# MCU.net
KiCad netlist of a schematic drawn in Altium Designer
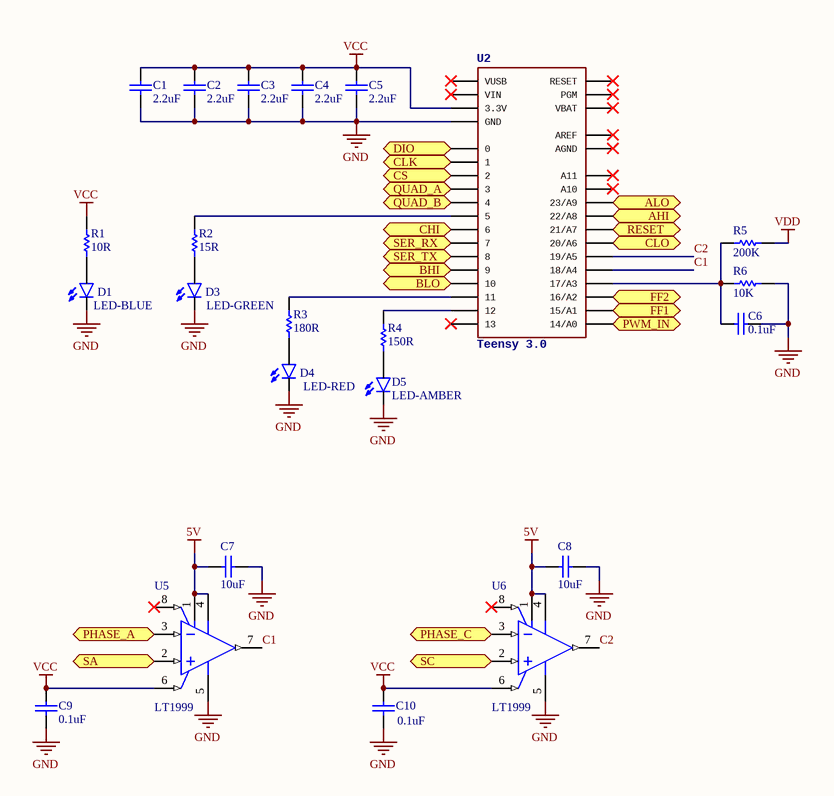
[diagram p0: MCU.SchDoc]

(export (version "E")
  (design (tool "Eeschema 10.0.6"))
  (components
    (comp (ref "C1")
      (value "2.2uF")
      (footprint "CAPC0603(1608)55_N")
      (description "CAP 2.2uF 16V Â±10% 0603 (1608 Metric) Thickness 0.55mm SMD")
      (fields (field (name "TOLERANCE") "Â±10%"))
      (libsource (lib "Altium Content Vault") (part "CMP-1035-02762-1"))
    )
    (comp (ref "C2")
      (value "2.2uF")
      (footprint "CAPC0603(1608)55_N")
      (description "CAP 2.2uF 16V Â±10% 0603 (1608 Metric) Thickness 0.55mm SMD")
      (fields (field (name "TOLERANCE") "Â±10%"))
      (libsource (lib "Altium Content Vault") (part "CMP-1035-02762-1"))
    )
    (comp (ref "C3")
      (value "2.2uF")
      (footprint "CAPC0603(1608)55_N")
      (description "CAP 2.2uF 16V Â±10% 0603 (1608 Metric) Thickness 0.55mm SMD")
      (fields (field (name "TOLERANCE") "Â±10%"))
      (libsource (lib "Altium Content Vault") (part "CMP-1035-02762-1"))
    )
    (comp (ref "C4")
      (value "2.2uF")
      (footprint "CAPC0603(1608)55_N")
      (description "CAP 2.2uF 16V Â±10% 0603 (1608 Metric) Thickness 0.55mm SMD")
      (fields (field (name "TOLERANCE") "Â±10%"))
      (libsource (lib "Altium Content Vault") (part "CMP-1035-02762-1"))
    )
    (comp (ref "C5")
      (value "2.2uF")
      (footprint "CAPC0603(1608)55_N")
      (description "CAP 2.2uF 16V Â±10% 0603 (1608 Metric) Thickness 0.55mm SMD")
      (fields (field (name "TOLERANCE") "Â±10%"))
      (libsource (lib "Altium Content Vault") (part "CMP-1035-02762-1"))
    )
    (comp (ref "C6")
      (value "0.1uF")
      (footprint "CAPC0603(1608)100_L")
      (description "CAP 100nF 50V Â±5% 0603 (1608 Metric) Thickness 1mm SMD")
      (fields (field (name "TOLERANCE") "Â±5%"))
      (libsource (lib "Altium Content Vault") (part "CMP-1035-02591-1"))
    )
    (comp (ref "C7")
      (value "10uF")
      (footprint "CAPC0603(1608)100_L")
      (description "CAP 10uF 6.3V Â±10% 0603 (1608 Metric) Thickness 1mm SMD")
      (fields (field (name "TOLERANCE") "Â±10%"))
      (libsource (lib "Altium Content Vault") (part "CMP-1035-02796-1"))
    )
    (comp (ref "C8")
      (value "10uF")
      (footprint "CAPC0603(1608)100_M")
      (description "CAP 10uF 6.3V Â±20% 0603 (1608 Metric) Thickness 1mm SMD")
      (fields (field (name "TOLERANCE") "Â±20%"))
      (libsource (lib "Altium Content Vault") (part "CMP-1035-02797-1"))
    )
    (comp (ref "C9")
      (value "0.1uF")
      (footprint "CAPC0603(1608)100_L")
      (description "CAP 100nF 6.3V Â±20% 0603 (1608 Metric) Thickness 1mm SMD")
      (fields (field (name "TOLERANCE") "Â±20%"))
      (libsource (lib "Altium Content Vault") (part "CMP-1035-02577-1"))
    )
    (comp (ref "C10")
      (value "0.1uF")
      (footprint "CAPC0603(1608)100_L")
      (description "CAP 100nF 6.3V Â±20% 0603 (1608 Metric) Thickness 1mm SMD")
      (fields (field (name "TOLERANCE") "Â±20%"))
      (libsource (lib "Altium Content Vault") (part "CMP-1035-02577-1"))
    )
    (comp (ref "D1")
      (value "LED-BLUE")
      (footprint "LED-1206")
      (libsource (lib "Components") (part "LED-BLUE1206"))
    )
    (comp (ref "D3")
      (value "LED-GREEN")
      (footprint "LED-1206")
      (libsource (lib "Components") (part "LED-GREEN1206"))
    )
    (comp (ref "D4")
      (value "LED-RED")
      (footprint "LED-1206")
      (libsource (lib "Components") (part "LED-RED1206"))
    )
    (comp (ref "D5")
      (value "LED-AMBER")
      (footprint "LED-1206")
      (libsource (lib "Components") (part "LED-AMBER1206"))
    )
    (comp (ref "R1")
      (value "10R")
      (footprint "RESC0603(1608)_N")
      (description "10R 0.1W 5% 0603 (1608 Metric)  SMD")
      (fields (field (name "TOLERANCE") "5 %") (field (name "POWER") "0.1 W"))
      (libsource (lib "Altium Content Vault") (part "CMP-1012-00026-1"))
    )
    (comp (ref "R2")
      (value "15R")
      (footprint "RESC0603(1608)_N")
      (description "15R 0.1W 5% 0603 (1608 Metric)  SMD")
      (fields (field (name "TOLERANCE") "5 %") (field (name "POWER") "0.1 W"))
      (libsource (lib "Altium Content Vault") (part "CMP-1012-00030-1"))
    )
    (comp (ref "R3")
      (value "180R")
      (footprint "RESC0603(1608)_N")
      (description "180R 0.1W 5% 0603 (1608 Metric)  SMD")
      (fields (field (name "POWER") "0.1 W") (field (name "TOLERANCE") "5 %"))
      (libsource (lib "Altium Content Vault") (part "CMP-1012-00056-1"))
    )
    (comp (ref "R4")
      (value "150R")
      (footprint "RESC0603(1608)_N")
      (description "150R 0.1W 5% 0603 (1608 Metric)  SMD")
      (fields (field (name "POWER") "0.1 W") (field (name "TOLERANCE") "5 %"))
      (libsource (lib "Altium Content Vault") (part "CMP-1012-00054-1"))
    )
    (comp (ref "R5")
      (value "200K")
      (footprint "RESC0603(1608)_N")
      (description "200K 0.1W 5% 0603 (1608 Metric)  SMD")
      (fields (field (name "POWER") "0.1 W") (field (name "TOLERANCE") "5 %"))
      (libsource (lib "Altium Content Vault") (part "CMP-1012-00129-1"))
    )
    (comp (ref "R6")
      (value "10K")
      (footprint "RESC0603(1608)_N")
      (description "10K 0.1W 5% 0603 (1608 Metric)  SMD")
      (fields (field (name "TOLERANCE") "5 %") (field (name "POWER") "0.1 W"))
      (libsource (lib "Altium Content Vault") (part "RES"))
    )
    (comp (ref "U2")
      (value "Teensy 3.0")
      (footprint "TEENSY_3.0+4")
      (libsource (lib "Teensy3.0") (part "TEENSY_3.0+4"))
    )
    (comp (ref "U5")
      (value "LT1999")
      (footprint "LT-MS8-8_N")
      (fields
        (field (name "MANUFACTURER") "Linear Technology")
        (field (name "PARTNUMBER") "LT1999HMS8-20#TRPBF")
        (field (name "LINEAR TECHNOLOGY PART NUMBER") "LT1999-20")
      )
      (libsource (lib "Altium Content Vault") (part "LT-LT1999-20-MS8-8"))
    )
    (comp (ref "U6")
      (value "LT1999")
      (footprint "LT-MS8-8_N")
      (fields
        (field (name "MANUFACTURER") "Linear Technology")
        (field (name "PARTNUMBER") "LT1999HMS8-20#TRPBF")
        (field (name "LINEAR TECHNOLOGY PART NUMBER") "LT1999-20")
      )
      (libsource (lib "Altium Content Vault") (part "LT-LT1999-20-MS8-8"))
    )
  )
  (nets
    (net (code "1") (name "/AHI") (class "Default")
      (node (ref "U2") (pin "22/A8") (pinfunction "22/A8_22/A8") (pintype "passive"))
    )
    (net (code "2") (name "/ALO") (class "Default")
      (node (ref "U2") (pin "23/A9") (pinfunction "23/A9_23/A9") (pintype "passive"))
    )
    (net (code "3") (name "/BHI") (class "Default")
      (node (ref "U2") (pin "9") (pinfunction "9_9") (pintype "passive"))
    )
    (net (code "4") (name "/BLO") (class "Default")
      (node (ref "U2") (pin "10") (pinfunction "10_10") (pintype "passive"))
    )
    (net (code "5") (name "/C1") (class "Default")
      (node (ref "U2") (pin "18/A4") (pinfunction "18/A4_18/A4") (pintype "passive"))
      (node (ref "U5") (pin "7") (pinfunction "OUT_7") (pintype "output"))
    )
    (net (code "6") (name "/C2") (class "Default")
      (node (ref "U2") (pin "19/A5") (pinfunction "19/A5_19/A5") (pintype "passive"))
      (node (ref "U6") (pin "7") (pinfunction "OUT_7") (pintype "output"))
    )
    (net (code "7") (name "/CHI") (class "Default")
      (node (ref "U2") (pin "6") (pinfunction "6_6") (pintype "passive"))
    )
    (net (code "8") (name "/CLK") (class "Default")
      (node (ref "U2") (pin "1") (pinfunction "1_1") (pintype "passive"))
    )
    (net (code "9") (name "/CLO") (class "Default")
      (node (ref "U2") (pin "20/A6") (pinfunction "20/A6_20/A6") (pintype "passive"))
    )
    (net (code "10") (name "/CS") (class "Default")
      (node (ref "U2") (pin "2") (pinfunction "2_2") (pintype "passive"))
    )
    (net (code "11") (name "/DIO") (class "Default")
      (node (ref "U2") (pin "0") (pinfunction "0_0") (pintype "passive"))
    )
    (net (code "12") (name "/FF1") (class "Default")
      (node (ref "U2") (pin "15/A1") (pinfunction "15/A1_15/A1") (pintype "passive"))
    )
    (net (code "13") (name "/FF2") (class "Default")
      (node (ref "U2") (pin "16/A2") (pinfunction "16/A2_16/A2") (pintype "passive"))
    )
    (net (code "14") (name "/PHASE_A") (class "Default")
      (node (ref "U5") (pin "3") (pinfunction "-IN_3") (pintype "input"))
    )
    (net (code "15") (name "/PHASE_C") (class "Default")
      (node (ref "U6") (pin "3") (pinfunction "-IN_3") (pintype "input"))
    )
    (net (code "16") (name "/PWM_IN") (class "Default")
      (node (ref "U2") (pin "14/A0") (pinfunction "14/A0_14/A0") (pintype "passive"))
    )
    (net (code "17") (name "/QUAD_A") (class "Default")
      (node (ref "U2") (pin "3") (pinfunction "3_3") (pintype "passive"))
    )
    (net (code "18") (name "/QUAD_B") (class "Default")
      (node (ref "U2") (pin "4") (pinfunction "4_4") (pintype "passive"))
    )
    (net (code "19") (name "/RESET") (class "Default")
      (node (ref "U2") (pin "21/A7") (pinfunction "21/A7_21/A7") (pintype "passive"))
    )
    (net (code "20") (name "/SA") (class "Default")
      (node (ref "U5") (pin "2") (pinfunction "+IN_2") (pintype "input"))
    )
    (net (code "21") (name "/SC") (class "Default")
      (node (ref "U6") (pin "2") (pinfunction "+IN_2") (pintype "input"))
    )
    (net (code "22") (name "/SER_RX") (class "Default")
      (node (ref "U2") (pin "7") (pinfunction "7_7") (pintype "passive"))
    )
    (net (code "23") (name "/SER_TX") (class "Default")
      (node (ref "U2") (pin "8") (pinfunction "8_8") (pintype "passive"))
    )
    (net (code "24") (name "5V") (class "Default")
      (node (ref "C7") (pin "1") (pinfunction "1_1") (pintype "passive"))
      (node (ref "C8") (pin "1") (pinfunction "1_1") (pintype "passive"))
      (node (ref "U5") (pin "1") (pinfunction "V+_1") (pintype "power_in"))
      (node (ref "U5") (pin "4") (pinfunction "V+_4") (pintype "power_in"))
      (node (ref "U6") (pin "1") (pinfunction "V+_1") (pintype "power_in"))
      (node (ref "U6") (pin "4") (pinfunction "V+_4") (pintype "power_in"))
    )
    (net (code "25") (name "GND") (class "Default")
      (node (ref "C1") (pin "1") (pinfunction "1_1") (pintype "passive"))
      (node (ref "C10") (pin "1") (pinfunction "1_1") (pintype "passive"))
      (node (ref "C2") (pin "1") (pinfunction "1_1") (pintype "passive"))
      (node (ref "C3") (pin "1") (pinfunction "1_1") (pintype "passive"))
      (node (ref "C4") (pin "1") (pinfunction "1_1") (pintype "passive"))
      (node (ref "C5") (pin "1") (pinfunction "1_1") (pintype "passive"))
      (node (ref "C6") (pin "2") (pinfunction "2_2") (pintype "passive"))
      (node (ref "C7") (pin "2") (pinfunction "2_2") (pintype "passive"))
      (node (ref "C8") (pin "2") (pinfunction "2_2") (pintype "passive"))
      (node (ref "C9") (pin "1") (pinfunction "1_1") (pintype "passive"))
      (node (ref "D1") (pin "C") (pinfunction "C_C") (pintype "passive"))
      (node (ref "D3") (pin "C") (pinfunction "C_C") (pintype "passive"))
      (node (ref "D4") (pin "C") (pinfunction "C_C") (pintype "passive"))
      (node (ref "D5") (pin "C") (pinfunction "C_C") (pintype "passive"))
      (node (ref "R6") (pin "2") (pinfunction "2_2") (pintype "passive"))
      (node (ref "U2") (pin "GND_GND1") (pinfunction "GND_GND_GND1") (pintype "power_in"))
      (node (ref "U5") (pin "5") (pinfunction "GND_5") (pintype "power_in"))
      (node (ref "U6") (pin "5") (pinfunction "GND_5") (pintype "power_in"))
    )
    (net (code "26") (name "Net-(C6-Pad1)") (class "Default")
      (node (ref "C6") (pin "1") (pinfunction "1_1") (pintype "passive"))
      (node (ref "R5") (pin "1") (pinfunction "1_1") (pintype "passive"))
      (node (ref "R6") (pin "1") (pinfunction "1_1") (pintype "passive"))
      (node (ref "U2") (pin "17/A3") (pinfunction "17/A3_17/A3") (pintype "passive"))
    )
    (net (code "27") (name "Net-(D1-PadA)") (class "Default")
      (node (ref "D1") (pin "A") (pinfunction "A_A") (pintype "passive"))
      (node (ref "R1") (pin "1") (pinfunction "1_1") (pintype "passive"))
    )
    (net (code "28") (name "Net-(D3-PadA)") (class "Default")
      (node (ref "D3") (pin "A") (pinfunction "A_A") (pintype "passive"))
      (node (ref "R2") (pin "1") (pinfunction "1_1") (pintype "passive"))
    )
    (net (code "29") (name "Net-(D4-PadA)") (class "Default")
      (node (ref "D4") (pin "A") (pinfunction "A_A") (pintype "passive"))
      (node (ref "R3") (pin "1") (pinfunction "1_1") (pintype "passive"))
    )
    (net (code "30") (name "Net-(D5-PadA)") (class "Default")
      (node (ref "D5") (pin "A") (pinfunction "A_A") (pintype "passive"))
      (node (ref "R4") (pin "1") (pinfunction "1_1") (pintype "passive"))
    )
    (net (code "31") (name "Net-(R2-Pad2)") (class "Default")
      (node (ref "R2") (pin "2") (pinfunction "2_2") (pintype "passive"))
      (node (ref "U2") (pin "5") (pinfunction "5_5") (pintype "passive"))
    )
    (net (code "32") (name "Net-(R3-Pad2)") (class "Default")
      (node (ref "R3") (pin "2") (pinfunction "2_2") (pintype "passive"))
      (node (ref "U2") (pin "11") (pinfunction "11_11") (pintype "passive"))
    )
    (net (code "33") (name "Net-(R4-Pad2)") (class "Default")
      (node (ref "R4") (pin "2") (pinfunction "2_2") (pintype "passive"))
      (node (ref "U2") (pin "12") (pinfunction "12_12") (pintype "passive"))
    )
    (net (code "34") (name "VCC") (class "Default")
      (node (ref "C1") (pin "2") (pinfunction "2_2") (pintype "passive"))
      (node (ref "C10") (pin "2") (pinfunction "2_2") (pintype "passive"))
      (node (ref "C2") (pin "2") (pinfunction "2_2") (pintype "passive"))
      (node (ref "C3") (pin "2") (pinfunction "2_2") (pintype "passive"))
      (node (ref "C4") (pin "2") (pinfunction "2_2") (pintype "passive"))
      (node (ref "C5") (pin "2") (pinfunction "2_2") (pintype "passive"))
      (node (ref "C9") (pin "2") (pinfunction "2_2") (pintype "passive"))
      (node (ref "R1") (pin "2") (pinfunction "2_2") (pintype "passive"))
      (node (ref "U2") (pin "3.3V_3.3V1") (pinfunction "3.3V_3.3V_3.3V1") (pintype "power_in"))
      (node (ref "U5") (pin "6") (pinfunction "REF_6") (pintype "input"))
      (node (ref "U6") (pin "6") (pinfunction "REF_6") (pintype "input"))
    )
    (net (code "35") (name "VDD") (class "Default")
      (node (ref "R5") (pin "2") (pinfunction "2_2") (pintype "passive"))
    )
    (net (code "36") (name "unconnected-(U2-Pad13)") (class "Default")
      (node (ref "U2") (pin "13") (pinfunction "13_13") (pintype "passive+no_connect"))
    )
    (net (code "37") (name "unconnected-(U2-PadA10)") (class "Default")
      (node (ref "U2") (pin "A10") (pinfunction "A10_A10") (pintype "passive+no_connect"))
    )
    (net (code "38") (name "unconnected-(U2-PadA11)") (class "Default")
      (node (ref "U2") (pin "A11") (pinfunction "A11_A11") (pintype "passive+no_connect"))
    )
    (net (code "39") (name "unconnected-(U2-PadAGND)") (class "Default")
      (node (ref "U2") (pin "AGND") (pinfunction "AGND_AGND") (pintype "power_in+no_connect"))
    )
    (net (code "40") (name "unconnected-(U2-PadAREF)") (class "Default")
      (node (ref "U2") (pin "AREF") (pinfunction "AREF_AREF") (pintype "power_in+no_connect"))
    )
    (net (code "41") (name "unconnected-(U2-PadPGM)") (class "Default")
      (node (ref "U2") (pin "PGM") (pinfunction "PGM_PGM") (pintype "passive+no_connect"))
    )
    (net (code "42") (name "unconnected-(U2-PadRESET)") (class "Default")
      (node (ref "U2") (pin "RESET") (pinfunction "RESET_RESET") (pintype "passive+no_connect"))
    )
    (net (code "43") (name "unconnected-(U2-PadVBAT)") (class "Default")
      (node (ref "U2") (pin "VBAT") (pinfunction "VBAT_VBAT") (pintype "power_in+no_connect"))
    )
    (net (code "44") (name "unconnected-(U2-PadVIN)") (class "Default")
      (node (ref "U2") (pin "VIN") (pinfunction "VIN_VIN") (pintype "power_in+no_connect"))
    )
    (net (code "45") (name "unconnected-(U2-PadVUSB)") (class "Default")
      (node (ref "U2") (pin "VUSB") (pinfunction "VUSB_VUSB") (pintype "power_in+no_connect"))
    )
    (net (code "46") (name "unconnected-(U5-~{SHDN}-Pad8)") (class "Default")
      (node (ref "U5") (pin "8") (pinfunction "~{SHDN}_8") (pintype "input+no_connect"))
    )
    (net (code "47") (name "unconnected-(U6-~{SHDN}-Pad8)") (class "Default")
      (node (ref "U6") (pin "8") (pinfunction "~{SHDN}_8") (pintype "input+no_connect"))
    )
  )
)
